# 09_USB_HDMI.net
KiCad netlist of a schematic drawn in Altium Designer
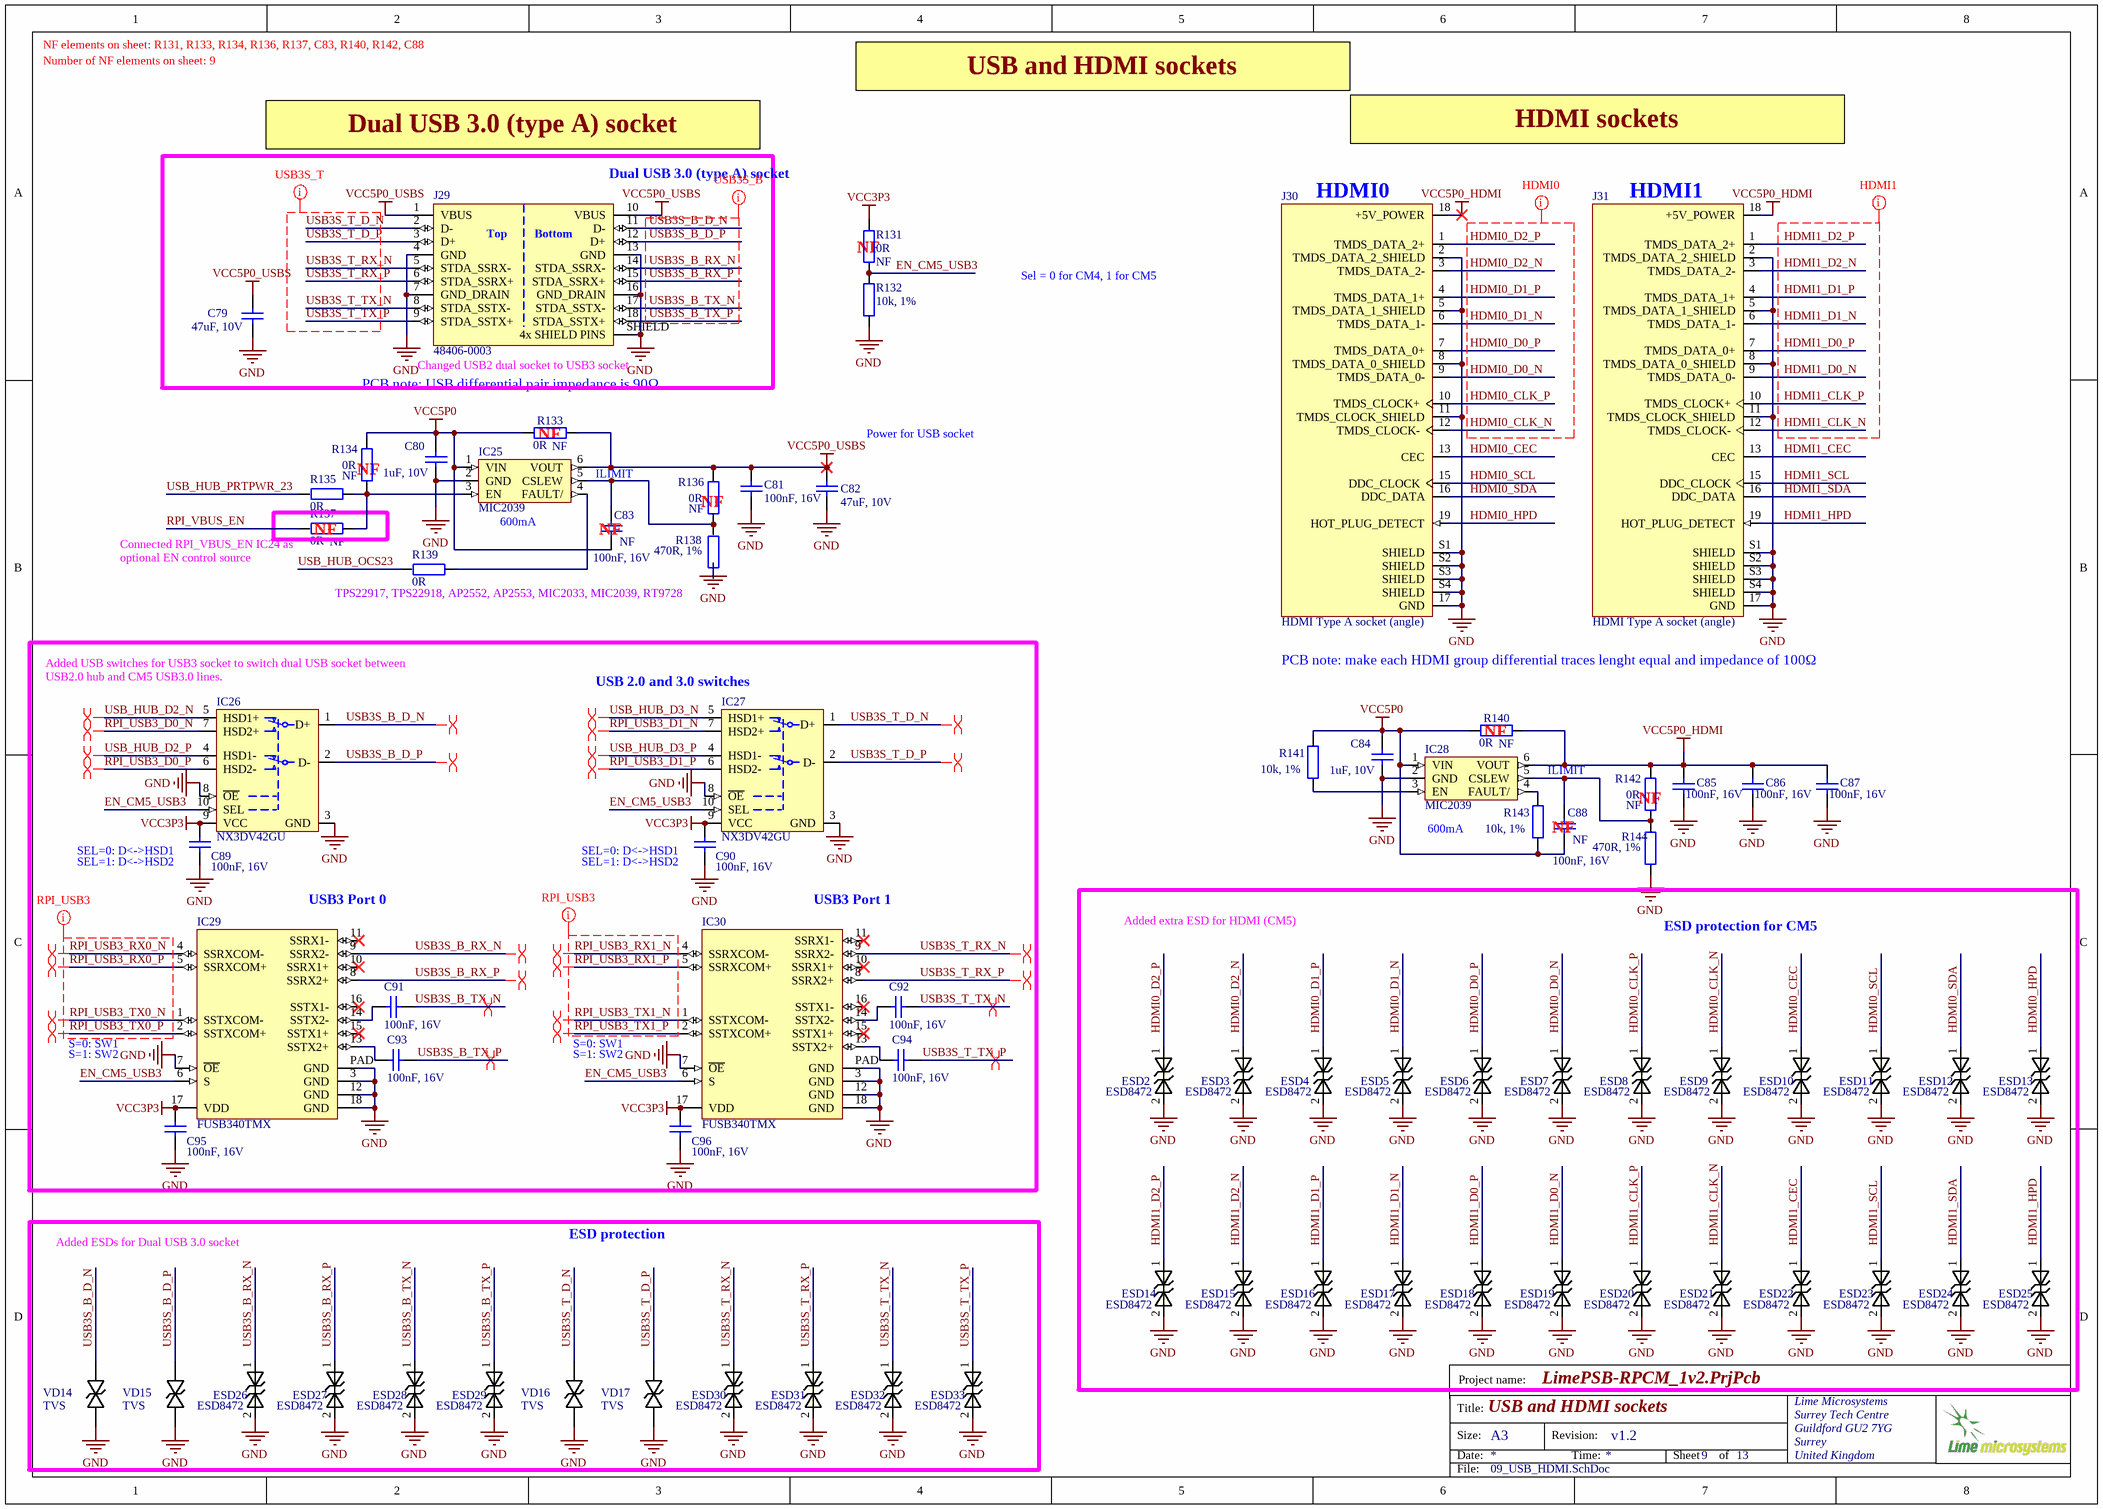
[diagram p0: 09_USB_HDMI.SchDoc]

(export (version "E")
  (design (tool "Eeschema 10.0.6"))
  (components
    (comp (ref "C79")
      (value "47uF, 10V")
      (footprint "CAP1206")
      (fields (field (name "TOLERANCE") "±20%") (field (name "MANUFACTURER") "TDK Corporation"))
      (libsource (lib "LimeFPGAboard_schLib") (part "Cap_1206"))
    )
    (comp (ref "C80")
      (value "1uF, 10V")
      (footprint "CAP0402")
      (fields (field (name "MANUFACTURER") "Yageo"))
      (libsource (lib "") (part "Cap_0402_1"))
    )
    (comp (ref "C81")
      (value "100nF, 16V")
      (footprint "CAP0402")
      (fields
        (field (name "MANUFACTURER") "Murata Electronics")
        (field (name "TOLERANCE") "10 %")
        (field (name "MANUFACTURER PART NUMBER") "GRM155R71C104KA88D")
      )
      (libsource (lib "") (part "Cap_0402_1"))
    )
    (comp (ref "C82")
      (value "47uF, 10V")
      (footprint "CAP1206")
      (fields (field (name "TOLERANCE") "±20%") (field (name "MANUFACTURER") "TDK Corporation"))
      (libsource (lib "LimeFPGAboard_schLib") (part "Cap_1206"))
    )
    (comp (ref "C83")
      (value "100nF, 16V")
      (footprint "CAP0402")
      (fields
        (field (name "ASSEMBLY INFO") "NF")
        (field (name "MANUFACTURER") "Murata Electronics")
        (field (name "TOLERANCE") "10 %")
        (field (name "MANUFACTURER PART NUMBER") "GRM155R71C104KA88D")
      )
      (libsource (lib "") (part "Cap_0402_1"))
    )
    (comp (ref "C84")
      (value "1uF, 10V")
      (footprint "CAP0402")
      (fields (field (name "MANUFACTURER") "Yageo"))
      (libsource (lib "") (part "Cap_0402_1"))
    )
    (comp (ref "C85")
      (value "100nF, 16V")
      (footprint "CAP0402")
      (fields
        (field (name "MANUFACTURER") "Murata Electronics")
        (field (name "TOLERANCE") "10 %")
        (field (name "MANUFACTURER PART NUMBER") "GRM155R71C104KA88D")
      )
      (libsource (lib "") (part "Cap_0402_1"))
    )
    (comp (ref "C86")
      (value "100nF, 16V")
      (footprint "CAP0402")
      (fields
        (field (name "MANUFACTURER") "Murata Electronics")
        (field (name "TOLERANCE") "10 %")
        (field (name "MANUFACTURER PART NUMBER") "GRM155R71C104KA88D")
      )
      (libsource (lib "") (part "Cap_0402_1"))
    )
    (comp (ref "C87")
      (value "100nF, 16V")
      (footprint "CAP0402")
      (fields
        (field (name "MANUFACTURER") "Murata Electronics")
        (field (name "TOLERANCE") "10 %")
        (field (name "MANUFACTURER PART NUMBER") "GRM155R71C104KA88D")
      )
      (libsource (lib "") (part "Cap_0402_1"))
    )
    (comp (ref "C88")
      (value "100nF, 16V")
      (footprint "CAP0402")
      (fields
        (field (name "ASSEMBLY INFO") "NF")
        (field (name "MANUFACTURER") "Murata Electronics")
        (field (name "TOLERANCE") "10 %")
        (field (name "MANUFACTURER PART NUMBER") "GRM155R71C104KA88D")
      )
      (libsource (lib "") (part "Cap_0402_1"))
    )
    (comp (ref "C89")
      (value "100nF, 16V")
      (footprint "CAP0402")
      (fields
        (field (name "MANUFACTURER") "Murata Electronics")
        (field (name "TOLERANCE") "10 %")
        (field (name "MANUFACTURER PART NUMBER") "GRM155R71C104KA88D")
      )
      (libsource (lib "LimeMicroAltiumLib_schLib") (part "Cap_0402"))
    )
    (comp (ref "C90")
      (value "100nF, 16V")
      (footprint "CAP0402")
      (fields
        (field (name "MANUFACTURER") "Murata Electronics")
        (field (name "TOLERANCE") "10 %")
        (field (name "MANUFACTURER PART NUMBER") "GRM155R71C104KA88D")
      )
      (libsource (lib "LimeMicroAltiumLib_schLib") (part "Cap_0402"))
    )
    (comp (ref "C91")
      (value "100nF, 16V")
      (footprint "CAP0402")
      (fields
        (field (name "MANUFACTURER") "Murata Electronics")
        (field (name "TOLERANCE") "10 %")
        (field (name "MANUFACTURER PART NUMBER") "GRM155R71C104KA88D")
      )
      (libsource (lib "LimeMicroAltiumLib_schLib") (part "Cap_0402"))
    )
    (comp (ref "C92")
      (value "100nF, 16V")
      (footprint "CAP0402")
      (fields
        (field (name "MANUFACTURER") "Murata Electronics")
        (field (name "TOLERANCE") "10 %")
        (field (name "MANUFACTURER PART NUMBER") "GRM155R71C104KA88D")
      )
      (libsource (lib "LimeMicroAltiumLib_schLib") (part "Cap_0402"))
    )
    (comp (ref "C93")
      (value "100nF, 16V")
      (footprint "CAP0402")
      (fields
        (field (name "MANUFACTURER") "Murata Electronics")
        (field (name "TOLERANCE") "10 %")
        (field (name "MANUFACTURER PART NUMBER") "GRM155R71C104KA88D")
      )
      (libsource (lib "LimeMicroAltiumLib_schLib") (part "Cap_0402"))
    )
    (comp (ref "C94")
      (value "100nF, 16V")
      (footprint "CAP0402")
      (fields
        (field (name "MANUFACTURER") "Murata Electronics")
        (field (name "TOLERANCE") "10 %")
        (field (name "MANUFACTURER PART NUMBER") "GRM155R71C104KA88D")
      )
      (libsource (lib "LimeMicroAltiumLib_schLib") (part "Cap_0402"))
    )
    (comp (ref "C95")
      (value "100nF, 16V")
      (footprint "CAP0402")
      (fields
        (field (name "MANUFACTURER") "Murata Electronics")
        (field (name "TOLERANCE") "10 %")
        (field (name "MANUFACTURER PART NUMBER") "GRM155R71C104KA88D")
      )
      (libsource (lib "LimeMicroAltiumLib_schLib") (part "Cap_0402"))
    )
    (comp (ref "C96")
      (value "100nF, 16V")
      (footprint "CAP0402")
      (fields
        (field (name "MANUFACTURER") "Murata Electronics")
        (field (name "TOLERANCE") "10 %")
        (field (name "MANUFACTURER PART NUMBER") "GRM155R71C104KA88D")
      )
      (libsource (lib "LimeMicroAltiumLib_schLib") (part "Cap_0402"))
    )
    (comp (ref "ESD2")
      (value "ESD8472")
      (footprint "ESD8472_X3DFN2")
      (fields (field (name "MANUFACTURER") "ON Semiconductor"))
      (libsource (lib "LimeMicroAltiumLib_schLib") (part "ESD8472"))
    )
    (comp (ref "ESD3")
      (value "ESD8472")
      (footprint "ESD8472_X3DFN2")
      (fields (field (name "MANUFACTURER") "ON Semiconductor"))
      (libsource (lib "LimeMicroAltiumLib_schLib") (part "ESD8472"))
    )
    (comp (ref "ESD4")
      (value "ESD8472")
      (footprint "ESD8472_X3DFN2")
      (fields (field (name "MANUFACTURER") "ON Semiconductor"))
      (libsource (lib "LimeMicroAltiumLib_schLib") (part "ESD8472"))
    )
    (comp (ref "ESD5")
      (value "ESD8472")
      (footprint "ESD8472_X3DFN2")
      (fields (field (name "MANUFACTURER") "ON Semiconductor"))
      (libsource (lib "LimeMicroAltiumLib_schLib") (part "ESD8472"))
    )
    (comp (ref "ESD6")
      (value "ESD8472")
      (footprint "ESD8472_X3DFN2")
      (fields (field (name "MANUFACTURER") "ON Semiconductor"))
      (libsource (lib "LimeMicroAltiumLib_schLib") (part "ESD8472"))
    )
    (comp (ref "ESD7")
      (value "ESD8472")
      (footprint "ESD8472_X3DFN2")
      (fields (field (name "MANUFACTURER") "ON Semiconductor"))
      (libsource (lib "LimeMicroAltiumLib_schLib") (part "ESD8472"))
    )
    (comp (ref "ESD8")
      (value "ESD8472")
      (footprint "ESD8472_X3DFN2")
      (fields (field (name "MANUFACTURER") "ON Semiconductor"))
      (libsource (lib "LimeMicroAltiumLib_schLib") (part "ESD8472"))
    )
    (comp (ref "ESD9")
      (value "ESD8472")
      (footprint "ESD8472_X3DFN2")
      (fields (field (name "MANUFACTURER") "ON Semiconductor"))
      (libsource (lib "LimeMicroAltiumLib_schLib") (part "ESD8472"))
    )
    (comp (ref "ESD10")
      (value "ESD8472")
      (footprint "ESD8472_X3DFN2")
      (fields (field (name "MANUFACTURER") "ON Semiconductor"))
      (libsource (lib "LimeMicroAltiumLib_schLib") (part "ESD8472"))
    )
    (comp (ref "ESD11")
      (value "ESD8472")
      (footprint "ESD8472_X3DFN2")
      (fields (field (name "MANUFACTURER") "ON Semiconductor"))
      (libsource (lib "LimeMicroAltiumLib_schLib") (part "ESD8472"))
    )
    (comp (ref "ESD12")
      (value "ESD8472")
      (footprint "ESD8472_X3DFN2")
      (fields (field (name "MANUFACTURER") "ON Semiconductor"))
      (libsource (lib "LimeMicroAltiumLib_schLib") (part "ESD8472"))
    )
    (comp (ref "ESD13")
      (value "ESD8472")
      (footprint "ESD8472_X3DFN2")
      (fields (field (name "MANUFACTURER") "ON Semiconductor"))
      (libsource (lib "LimeMicroAltiumLib_schLib") (part "ESD8472"))
    )
    (comp (ref "ESD14")
      (value "ESD8472")
      (footprint "ESD8472_X3DFN2")
      (fields (field (name "MANUFACTURER") "ON Semiconductor"))
      (libsource (lib "LimeMicroAltiumLib_schLib") (part "ESD8472"))
    )
    (comp (ref "ESD15")
      (value "ESD8472")
      (footprint "ESD8472_X3DFN2")
      (fields (field (name "MANUFACTURER") "ON Semiconductor"))
      (libsource (lib "LimeMicroAltiumLib_schLib") (part "ESD8472"))
    )
    (comp (ref "ESD16")
      (value "ESD8472")
      (footprint "ESD8472_X3DFN2")
      (fields (field (name "MANUFACTURER") "ON Semiconductor"))
      (libsource (lib "LimeMicroAltiumLib_schLib") (part "ESD8472"))
    )
    (comp (ref "ESD17")
      (value "ESD8472")
      (footprint "ESD8472_X3DFN2")
      (fields (field (name "MANUFACTURER") "ON Semiconductor"))
      (libsource (lib "LimeMicroAltiumLib_schLib") (part "ESD8472"))
    )
    (comp (ref "ESD18")
      (value "ESD8472")
      (footprint "ESD8472_X3DFN2")
      (fields (field (name "MANUFACTURER") "ON Semiconductor"))
      (libsource (lib "LimeMicroAltiumLib_schLib") (part "ESD8472"))
    )
    (comp (ref "ESD19")
      (value "ESD8472")
      (footprint "ESD8472_X3DFN2")
      (fields (field (name "MANUFACTURER") "ON Semiconductor"))
      (libsource (lib "LimeMicroAltiumLib_schLib") (part "ESD8472"))
    )
    (comp (ref "ESD20")
      (value "ESD8472")
      (footprint "ESD8472_X3DFN2")
      (fields (field (name "MANUFACTURER") "ON Semiconductor"))
      (libsource (lib "LimeMicroAltiumLib_schLib") (part "ESD8472"))
    )
    (comp (ref "ESD21")
      (value "ESD8472")
      (footprint "ESD8472_X3DFN2")
      (fields (field (name "MANUFACTURER") "ON Semiconductor"))
      (libsource (lib "LimeMicroAltiumLib_schLib") (part "ESD8472"))
    )
    (comp (ref "ESD22")
      (value "ESD8472")
      (footprint "ESD8472_X3DFN2")
      (fields (field (name "MANUFACTURER") "ON Semiconductor"))
      (libsource (lib "LimeMicroAltiumLib_schLib") (part "ESD8472"))
    )
    (comp (ref "ESD23")
      (value "ESD8472")
      (footprint "ESD8472_X3DFN2")
      (fields (field (name "MANUFACTURER") "ON Semiconductor"))
      (libsource (lib "LimeMicroAltiumLib_schLib") (part "ESD8472"))
    )
    (comp (ref "ESD24")
      (value "ESD8472")
      (footprint "ESD8472_X3DFN2")
      (fields (field (name "MANUFACTURER") "ON Semiconductor"))
      (libsource (lib "LimeMicroAltiumLib_schLib") (part "ESD8472"))
    )
    (comp (ref "ESD25")
      (value "ESD8472")
      (footprint "ESD8472_X3DFN2")
      (fields (field (name "MANUFACTURER") "ON Semiconductor"))
      (libsource (lib "LimeMicroAltiumLib_schLib") (part "ESD8472"))
    )
    (comp (ref "ESD26")
      (value "ESD8472")
      (footprint "ESD8472_X3DFN2")
      (fields (field (name "MANUFACTURER") "ON Semiconductor"))
      (libsource (lib "LimeMicroAltiumLib_schLib") (part "ESD8472"))
    )
    (comp (ref "ESD27")
      (value "ESD8472")
      (footprint "ESD8472_X3DFN2")
      (fields (field (name "MANUFACTURER") "ON Semiconductor"))
      (libsource (lib "LimeMicroAltiumLib_schLib") (part "ESD8472"))
    )
    (comp (ref "ESD28")
      (value "ESD8472")
      (footprint "ESD8472_X3DFN2")
      (fields (field (name "MANUFACTURER") "ON Semiconductor"))
      (libsource (lib "LimeMicroAltiumLib_schLib") (part "ESD8472"))
    )
    (comp (ref "ESD29")
      (value "ESD8472")
      (footprint "ESD8472_X3DFN2")
      (fields (field (name "MANUFACTURER") "ON Semiconductor"))
      (libsource (lib "LimeMicroAltiumLib_schLib") (part "ESD8472"))
    )
    (comp (ref "ESD30")
      (value "ESD8472")
      (footprint "ESD8472_X3DFN2")
      (fields (field (name "MANUFACTURER") "ON Semiconductor"))
      (libsource (lib "LimeMicroAltiumLib_schLib") (part "ESD8472"))
    )
    (comp (ref "ESD31")
      (value "ESD8472")
      (footprint "ESD8472_X3DFN2")
      (fields (field (name "MANUFACTURER") "ON Semiconductor"))
      (libsource (lib "LimeMicroAltiumLib_schLib") (part "ESD8472"))
    )
    (comp (ref "ESD32")
      (value "ESD8472")
      (footprint "ESD8472_X3DFN2")
      (fields (field (name "MANUFACTURER") "ON Semiconductor"))
      (libsource (lib "LimeMicroAltiumLib_schLib") (part "ESD8472"))
    )
    (comp (ref "ESD33")
      (value "ESD8472")
      (footprint "ESD8472_X3DFN2")
      (fields (field (name "MANUFACTURER") "ON Semiconductor"))
      (libsource (lib "LimeMicroAltiumLib_schLib") (part "ESD8472"))
    )
    (comp (ref "IC25")
      (value "MIC2039")
      (footprint "SOT23-6")
      (fields (field (name "MANUFACTURER") "Microchip"))
      (libsource (lib "LimeMicroAltiumLib_schLib_r04") (part "MIC2033_power_switch"))
    )
    (comp (ref "IC26")
      (value "NX3DV42GU")
      (footprint "FSUSB42UMX")
      (fields (field (name "MANUFACTURER") "NXP Semiconductors"))
      (libsource (lib "LimeMicroAltiumLib_schLib_r01") (part "FSUSB42UMX"))
    )
    (comp (ref "IC27")
      (value "NX3DV42GU")
      (footprint "FSUSB42UMX")
      (fields (field (name "MANUFACTURER") "NXP Semiconductors"))
      (libsource (lib "LimeMicroAltiumLib_schLib_r01") (part "FSUSB42UMX"))
    )
    (comp (ref "IC28")
      (value "MIC2039")
      (footprint "SOT23-6")
      (fields (field (name "MANUFACTURER") "Microchip"))
      (libsource (lib "LimeMicroAltiumLib_schLib_r04") (part "MIC2033_power_switch"))
    )
    (comp (ref "IC29")
      (value "FUSB340TMX")
      (footprint "FUSB340TMX_USB_switch_18-XFQFN")
      (fields (field (name "MANUFACTURER") "ON Semiconductor / Fairchild"))
      (libsource (lib "LimeMicroAltiumLib") (part "FUSB340TMX_USB_switch"))
    )
    (comp (ref "IC30")
      (value "FUSB340TMX")
      (footprint "FUSB340TMX_USB_switch_18-XFQFN")
      (fields (field (name "MANUFACTURER") "ON Semiconductor / Fairchild"))
      (libsource (lib "LimeMicroAltiumLib") (part "FUSB340TMX_USB_switch"))
    )
    (comp (ref "J29")
      (value "48406-0003")
      (footprint "Dual_USB_48406-0003_Molex")
      (fields (field (name "MANUFACTURER") "Molex"))
      (libsource (lib "LimeMicroAltiumLib") (part "Dual_USB_48406-0003_Molex"))
    )
    (comp (ref "J30")
      (value "HDMI Type A socket (angle)")
      (footprint "HDMI_HD01-19-RA-TH")
      (fields (field (name "MANUFACTURER") "CUI Devices"))
      (libsource (lib "LimeMicroAltiumLib_schLib_r04") (part "HDMI_HD01-19-RA-TH"))
    )
    (comp (ref "J31")
      (value "HDMI Type A socket (angle)")
      (footprint "HDMI_HD01-19-RA-TH")
      (fields (field (name "MANUFACTURER") "CUI Devices"))
      (libsource (lib "LimeMicroAltiumLib_schLib_r04") (part "HDMI_HD01-19-RA-TH"))
    )
    (comp (ref "R131")
      (value "0R")
      (footprint "RES0402")
      (fields
        (field (name "ASSEMBLY INFO") "NF")
        (field (name "MANUFACTURER") "Yageo")
        (field (name "TOLERANCE") "Jumper")
      )
      (libsource (lib "") (part "Res_0402_1"))
    )
    (comp (ref "R132")
      (value "10k, 1%")
      (footprint "RES0402")
      (fields (field (name "MANUFACTURER") "Yageo") (field (name "TOLERANCE") "±1%"))
      (libsource (lib "") (part "Res_0402_1"))
    )
    (comp (ref "R133")
      (value "0R")
      (footprint "RES0402")
      (fields
        (field (name "ASSEMBLY INFO") "NF")
        (field (name "MANUFACTURER") "Yageo")
        (field (name "TOLERANCE") "Jumper")
      )
      (libsource (lib "LimeMicroAltiumLib_schLib") (part "Res_0402"))
    )
    (comp (ref "R134")
      (value "0R")
      (footprint "RES0402")
      (fields
        (field (name "ASSEMBLY INFO") "NF")
        (field (name "MANUFACTURER") "Yageo")
        (field (name "TOLERANCE") "Jumper")
      )
      (libsource (lib "LimeMicroAltiumLib_schLib") (part "Res_0402"))
    )
    (comp (ref "R135")
      (value "0R")
      (footprint "RES0402")
      (fields (field (name "MANUFACTURER") "Yageo") (field (name "TOLERANCE") "Jumper"))
      (libsource (lib "LimeMicroAltiumLib_schLib") (part "Res_0402"))
    )
    (comp (ref "R136")
      (value "0R")
      (footprint "RES0402")
      (fields
        (field (name "ASSEMBLY INFO") "NF")
        (field (name "MANUFACTURER") "Yageo")
        (field (name "TOLERANCE") "Jumper")
      )
      (libsource (lib "LimeMicroAltiumLib_schLib") (part "Res_0402"))
    )
    (comp (ref "R137")
      (value "0R")
      (footprint "RES0402")
      (fields
        (field (name "ASSEMBLY INFO") "NF")
        (field (name "MANUFACTURER") "Yageo")
        (field (name "TOLERANCE") "Jumper")
      )
      (libsource (lib "LimeMicroAltiumLib_schLib") (part "Res_0402"))
    )
    (comp (ref "R138")
      (value "470R, 1%")
      (footprint "RES0402")
      (fields (field (name "TOLERANCE") "1%") (field (name "MANUFACTURER") "Yageo"))
      (libsource (lib "LimeMicroAltiumLib_schLib") (part "Res_0402"))
    )
    (comp (ref "R139")
      (value "0R")
      (footprint "RES0402")
      (fields (field (name "MANUFACTURER") "Yageo") (field (name "TOLERANCE") "Jumper"))
      (libsource (lib "LimeMicroAltiumLib_schLib") (part "Res_0402"))
    )
    (comp (ref "R140")
      (value "0R")
      (footprint "RES0402")
      (fields
        (field (name "ASSEMBLY INFO") "NF")
        (field (name "MANUFACTURER") "Yageo")
        (field (name "TOLERANCE") "Jumper")
      )
      (libsource (lib "LimeMicroAltiumLib_schLib") (part "Res_0402"))
    )
    (comp (ref "R141")
      (value "10k, 1%")
      (footprint "RES0402")
      (fields (field (name "MANUFACTURER") "Yageo") (field (name "TOLERANCE") "±1%"))
      (libsource (lib "") (part "Res_0402_1"))
    )
    (comp (ref "R142")
      (value "0R")
      (footprint "RES0402")
      (fields
        (field (name "ASSEMBLY INFO") "NF")
        (field (name "MANUFACTURER") "Yageo")
        (field (name "TOLERANCE") "Jumper")
      )
      (libsource (lib "LimeMicroAltiumLib_schLib") (part "Res_0402"))
    )
    (comp (ref "R143")
      (value "10k, 1%")
      (footprint "RES0402")
      (fields (field (name "MANUFACTURER") "Yageo") (field (name "TOLERANCE") "±1%"))
      (libsource (lib "") (part "Res_0402_1"))
    )
    (comp (ref "R144")
      (value "470R, 1%")
      (footprint "RES0402")
      (fields (field (name "TOLERANCE") "1%") (field (name "MANUFACTURER") "Yageo"))
      (libsource (lib "LimeMicroAltiumLib_schLib") (part "Res_0402"))
    )
    (comp (ref "VD14")
      (value "TVS")
      (footprint "SOD323")
      (fields
        (field (name "MANUFACTURER PART NUMBER") "SD03LCC")
        (field (name "MANUFACTURER") "Sangdest Microelectronics")
      )
      (libsource (lib "LimeNet-Micro_2v1-SDR") (part "DIODE_TVS"))
    )
    (comp (ref "VD15")
      (value "TVS")
      (footprint "SOD323")
      (fields
        (field (name "MANUFACTURER PART NUMBER") "SD03LCC")
        (field (name "MANUFACTURER") "Sangdest Microelectronics")
      )
      (libsource (lib "LimeNet-Micro_2v1-SDR") (part "DIODE_TVS"))
    )
    (comp (ref "VD16")
      (value "TVS")
      (footprint "SOD323")
      (fields
        (field (name "MANUFACTURER PART NUMBER") "SD03LCC")
        (field (name "MANUFACTURER") "Sangdest Microelectronics")
      )
      (libsource (lib "LimeNet-Micro_2v1-SDR") (part "DIODE_TVS"))
    )
    (comp (ref "VD17")
      (value "TVS")
      (footprint "SOD323")
      (fields
        (field (name "MANUFACTURER PART NUMBER") "SD03LCC")
        (field (name "MANUFACTURER") "Sangdest Microelectronics")
      )
      (libsource (lib "LimeNet-Micro_2v1-SDR") (part "DIODE_TVS"))
    )
  )
  (nets
    (net (code "1") (name "/EN_CM5_USB3") (class "Default")
      (node (ref "IC26") (pin "10") (pinfunction "SEL_10") (pintype "input"))
      (node (ref "IC27") (pin "10") (pinfunction "SEL_10") (pintype "input"))
      (node (ref "IC29") (pin "6") (pinfunction "S_6") (pintype "input"))
      (node (ref "IC30") (pin "6") (pinfunction "S_6") (pintype "input"))
      (node (ref "R131") (pin "1") (pinfunction "1_1") (pintype "passive"))
      (node (ref "R132") (pin "1") (pinfunction "1_1") (pintype "passive"))
    )
    (net (code "2") (name "/HDMI0_CEC") (class "Default")
      (node (ref "ESD10") (pin "1") (pinfunction "1_1") (pintype "passive"))
      (node (ref "J30") (pin "13") (pinfunction "CEC_13") (pintype "bidirectional"))
    )
    (net (code "3") (name "/HDMI0_CLK_N") (class "Default")
      (node (ref "ESD9") (pin "1") (pinfunction "1_1") (pintype "passive"))
      (node (ref "J30") (pin "12") (pinfunction "TMDS_CLOCK-_12") (pintype "bidirectional"))
    )
    (net (code "4") (name "/HDMI0_CLK_P") (class "Default")
      (node (ref "ESD8") (pin "1") (pinfunction "1_1") (pintype "passive"))
      (node (ref "J30") (pin "10") (pinfunction "TMDS_CLOCK+_10") (pintype "bidirectional"))
    )
    (net (code "5") (name "/HDMI0_D0_N") (class "Default")
      (node (ref "ESD7") (pin "1") (pinfunction "1_1") (pintype "passive"))
      (node (ref "J30") (pin "9") (pinfunction "TMDS_DATA_0-_9") (pintype "bidirectional"))
    )
    (net (code "6") (name "/HDMI0_D0_P") (class "Default")
      (node (ref "ESD6") (pin "1") (pinfunction "1_1") (pintype "passive"))
      (node (ref "J30") (pin "7") (pinfunction "TMDS_DATA_0+_7") (pintype "bidirectional"))
    )
    (net (code "7") (name "/HDMI0_D1_N") (class "Default")
      (node (ref "ESD5") (pin "1") (pinfunction "1_1") (pintype "passive"))
      (node (ref "J30") (pin "6") (pinfunction "TMDS_DATA_1-_6") (pintype "bidirectional"))
    )
    (net (code "8") (name "/HDMI0_D1_P") (class "Default")
      (node (ref "ESD4") (pin "1") (pinfunction "1_1") (pintype "passive"))
      (node (ref "J30") (pin "4") (pinfunction "TMDS_DATA_1+_4") (pintype "bidirectional"))
    )
    (net (code "9") (name "/HDMI0_D2_N") (class "Default")
      (node (ref "ESD3") (pin "1") (pinfunction "1_1") (pintype "passive"))
      (node (ref "J30") (pin "3") (pinfunction "TMDS_DATA_2-_3") (pintype "bidirectional"))
    )
    (net (code "10") (name "/HDMI0_D2_P") (class "Default")
      (node (ref "ESD2") (pin "1") (pinfunction "1_1") (pintype "passive"))
      (node (ref "J30") (pin "1") (pinfunction "TMDS_DATA_2+_1") (pintype "bidirectional"))
    )
    (net (code "11") (name "/HDMI0_HPD") (class "Default")
      (node (ref "ESD13") (pin "1") (pinfunction "1_1") (pintype "passive"))
      (node (ref "J30") (pin "19") (pinfunction "HOT_PLUG_DETECT_19") (pintype "input"))
    )
    (net (code "12") (name "/HDMI0_SCL") (class "Default")
      (node (ref "ESD11") (pin "1") (pinfunction "1_1") (pintype "passive"))
      (node (ref "J30") (pin "15") (pinfunction "DDC_CLOCK_15") (pintype "bidirectional"))
    )
    (net (code "13") (name "/HDMI0_SDA") (class "Default")
      (node (ref "ESD12") (pin "1") (pinfunction "1_1") (pintype "passive"))
      (node (ref "J30") (pin "16") (pinfunction "DDC_DATA_16") (pintype "bidirectional"))
    )
    (net (code "14") (name "/HDMI1_CEC") (class "Default")
      (node (ref "ESD22") (pin "1") (pinfunction "1_1") (pintype "passive"))
      (node (ref "J31") (pin "13") (pinfunction "CEC_13") (pintype "bidirectional"))
    )
    (net (code "15") (name "/HDMI1_CLK_N") (class "Default")
      (node (ref "ESD21") (pin "1") (pinfunction "1_1") (pintype "passive"))
      (node (ref "J31") (pin "12") (pinfunction "TMDS_CLOCK-_12") (pintype "bidirectional"))
    )
    (net (code "16") (name "/HDMI1_CLK_P") (class "Default")
      (node (ref "ESD20") (pin "1") (pinfunction "1_1") (pintype "passive"))
      (node (ref "J31") (pin "10") (pinfunction "TMDS_CLOCK+_10") (pintype "bidirectional"))
    )
    (net (code "17") (name "/HDMI1_D0_N") (class "Default")
      (node (ref "ESD19") (pin "1") (pinfunction "1_1") (pintype "passive"))
      (node (ref "J31") (pin "9") (pinfunction "TMDS_DATA_0-_9") (pintype "bidirectional"))
    )
    (net (code "18") (name "/HDMI1_D0_P") (class "Default")
      (node (ref "ESD18") (pin "1") (pinfunction "1_1") (pintype "passive"))
      (node (ref "J31") (pin "7") (pinfunction "TMDS_DATA_0+_7") (pintype "bidirectional"))
    )
    (net (code "19") (name "/HDMI1_D1_N") (class "Default")
      (node (ref "ESD17") (pin "1") (pinfunction "1_1") (pintype "passive"))
      (node (ref "J31") (pin "6") (pinfunction "TMDS_DATA_1-_6") (pintype "bidirectional"))
    )
    (net (code "20") (name "/HDMI1_D1_P") (class "Default")
      (node (ref "ESD16") (pin "1") (pinfunction "1_1") (pintype "passive"))
      (node (ref "J31") (pin "4") (pinfunction "TMDS_DATA_1+_4") (pintype "bidirectional"))
    )
    (net (code "21") (name "/HDMI1_D2_N") (class "Default")
      (node (ref "ESD15") (pin "1") (pinfunction "1_1") (pintype "passive"))
      (node (ref "J31") (pin "3") (pinfunction "TMDS_DATA_2-_3") (pintype "bidirectional"))
    )
    (net (code "22") (name "/HDMI1_D2_P") (class "Default")
      (node (ref "ESD14") (pin "1") (pinfunction "1_1") (pintype "passive"))
      (node (ref "J31") (pin "1") (pinfunction "TMDS_DATA_2+_1") (pintype "bidirectional"))
    )
    (net (code "23") (name "/HDMI1_HPD") (class "Default")
      (node (ref "ESD25") (pin "1") (pinfunction "1_1") (pintype "passive"))
      (node (ref "J31") (pin "19") (pinfunction "HOT_PLUG_DETECT_19") (pintype "input"))
    )
    (net (code "24") (name "/HDMI1_SCL") (class "Default")
      (node (ref "ESD23") (pin "1") (pinfunction "1_1") (pintype "passive"))
      (node (ref "J31") (pin "15") (pinfunction "DDC_CLOCK_15") (pintype "bidirectional"))
    )
    (net (code "25") (name "/HDMI1_SDA") (class "Default")
      (node (ref "ESD24") (pin "1") (pinfunction "1_1") (pintype "passive"))
      (node (ref "J31") (pin "16") (pinfunction "DDC_DATA_16") (pintype "bidirectional"))
    )
    (net (code "26") (name "/RPI_USB3_D0_N") (class "Default")
      (node (ref "IC26") (pin "7") (pinfunction "HSD2+_7") (pintype "passive"))
    )
    (net (code "27") (name "/RPI_USB3_D0_P") (class "Default")
      (node (ref "IC26") (pin "6") (pinfunction "HSD2-_6") (pintype "passive"))
    )
    (net (code "28") (name "/RPI_USB3_D1_N") (class "Default")
      (node (ref "IC27") (pin "7") (pinfunction "HSD2+_7") (pintype "passive"))
    )
    (net (code "29") (name "/RPI_USB3_D1_P") (class "Default")
      (node (ref "IC27") (pin "6") (pinfunction "HSD2-_6") (pintype "passive"))
    )
    (net (code "30") (name "/RPI_USB3_RX0_N") (class "Default")
      (node (ref "IC29") (pin "4") (pinfunction "SSRXCOM-_4") (pintype "bidirectional"))
    )
    (net (code "31") (name "/RPI_USB3_RX0_P") (class "Default")
      (node (ref "IC29") (pin "5") (pinfunction "SSRXCOM+_5") (pintype "bidirectional"))
    )
    (net (code "32") (name "/RPI_USB3_RX1_N") (class "Default")
      (node (ref "IC30") (pin "4") (pinfunction "SSRXCOM-_4") (pintype "bidirectional"))
    )
    (net (code "33") (name "/RPI_USB3_RX1_P") (class "Default")
      (node (ref "IC30") (pin "5") (pinfunction "SSRXCOM+_5") (pintype "bidirectional"))
    )
    (net (code "34") (name "/RPI_USB3_TX0_N") (class "Default")
      (node (ref "IC29") (pin "1") (pinfunction "SSTXCOM-_1") (pintype "bidirectional"))
    )
    (net (code "35") (name "/RPI_USB3_TX0_P") (class "Default")
      (node (ref "IC29") (pin "2") (pinfunction "SSTXCOM+_2") (pintype "bidirectional"))
    )
    (net (code "36") (name "/RPI_USB3_TX1_N") (class "Default")
      (node (ref "IC30") (pin "1") (pinfunction "SSTXCOM-_1") (pintype "bidirectional"))
    )
    (net (code "37") (name "/RPI_USB3_TX1_P") (class "Default")
      (node (ref "IC30") (pin "2") (pinfunction "SSTXCOM+_2") (pintype "bidirectional"))
    )
    (net (code "38") (name "/RPI_VBUS_EN") (class "Default")
      (node (ref "R137") (pin "2") (pinfunction "2_2") (pintype "passive"))
    )
    (net (code "39") (name "/USB3S_B_D_N") (class "Default")
      (node (ref "IC26") (pin "1") (pinfunction "D+_1") (pintype "passive"))
      (node (ref "J29") (pin "11") (pinfunction "D-_11") (pintype "bidirectional"))
      (node (ref "VD14") (pin "A") (pinfunction "A_A") (pintype "passive"))
    )
    (net (code "40") (name "/USB3S_B_D_P") (class "Default")
      (node (ref "IC26") (pin "2") (pinfunction "D-_2") (pintype "passive"))
      (node (ref "J29") (pin "12") (pinfunction "D+_12") (pintype "bidirectional"))
      (node (ref "VD15") (pin "A") (pinfunction "A_A") (pintype "passive"))
    )
    (net (code "41") (name "/USB3S_B_RX_N") (class "Default")
      (node (ref "ESD26") (pin "1") (pinfunction "1_1") (pintype "passive"))
      (node (ref "IC29") (pin "9") (pinfunction "SSRX2-_9") (pintype "bidirectional"))
      (node (ref "J29") (pin "14") (pinfunction "STDA_SSRX-_14") (pintype "bidirectional"))
    )
    (net (code "42") (name "/USB3S_B_RX_P") (class "Default")
      (node (ref "ESD27") (pin "1") (pinfunction "1_1") (pintype "passive"))
      (node (ref "IC29") (pin "8") (pinfunction "SSRX2+_8") (pintype "bidirectional"))
      (node (ref "J29") (pin "15") (pinfunction "STDA_SSRX+_15") (pintype "bidirectional"))
    )
    (net (code "43") (name "/USB3S_B_TX_N") (class "Default")
      (node (ref "C91") (pin "2") (pinfunction "2_2") (pintype "passive"))
      (node (ref "ESD28") (pin "1") (pinfunction "1_1") (pintype "passive"))
      (node (ref "J29") (pin "17") (pinfunction "STDA_SSTX-_17") (pintype "bidirectional"))
    )
    (net (code "44") (name "/USB3S_B_TX_P") (class "Default")
      (node (ref "C93") (pin "2") (pinfunction "2_2") (pintype "passive"))
      (node (ref "ESD29") (pin "1") (pinfunction "1_1") (pintype "passive"))
      (node (ref "J29") (pin "18") (pinfunction "STDA_SSTX+_18") (pintype "bidirectional"))
    )
    (net (code "45") (name "/USB3S_T_D_N") (class "Default")
      (node (ref "IC27") (pin "1") (pinfunction "D+_1") (pintype "passive"))
      (node (ref "J29") (pin "2") (pinfunction "D-_2") (pintype "bidirectional"))
      (node (ref "VD16") (pin "A") (pinfunction "A_A") (pintype "passive"))
    )
    (net (code "46") (name "/USB3S_T_D_P") (class "Default")
      (node (ref "IC27") (pin "2") (pinfunction "D-_2") (pintype "passive"))
      (node (ref "J29") (pin "3") (pinfunction "D+_3") (pintype "bidirectional"))
      (node (ref "VD17") (pin "A") (pinfunction "A_A") (pintype "passive"))
    )
    (net (code "47") (name "/USB3S_T_RX_N") (class "Default")
      (node (ref "ESD30") (pin "1") (pinfunction "1_1") (pintype "passive"))
      (node (ref "IC30") (pin "9") (pinfunction "SSRX2-_9") (pintype "bidirectional"))
      (node (ref "J29") (pin "5") (pinfunction "STDA_SSRX-_5") (pintype "bidirectional"))
    )
    (net (code "48") (name "/USB3S_T_RX_P") (class "Default")
      (node (ref "ESD31") (pin "1") (pinfunction "1_1") (pintype "passive"))
      (node (ref "IC30") (pin "8") (pinfunction "SSRX2+_8") (pintype "bidirectional"))
      (node (ref "J29") (pin "6") (pinfunction "STDA_SSRX+_6") (pintype "bidirectional"))
    )
    (net (code "49") (name "/USB3S_T_TX_N") (class "Default")
      (node (ref "C92") (pin "2") (pinfunction "2_2") (pintype "passive"))
      (node (ref "ESD32") (pin "1") (pinfunction "1_1") (pintype "passive"))
      (node (ref "J29") (pin "8") (pinfunction "STDA_SSTX-_8") (pintype "bidirectional"))
    )
    (net (code "50") (name "/USB3S_T_TX_P") (class "Default")
      (node (ref "C94") (pin "2") (pinfunction "2_2") (pintype "passive"))
      (node (ref "ESD33") (pin "1") (pinfunction "1_1") (pintype "passive"))
      (node (ref "J29") (pin "9") (pinfunction "STDA_SSTX+_9") (pintype "bidirectional"))
    )
    (net (code "51") (name "/USB_HUB_D2_N") (class "Default")
      (node (ref "IC26") (pin "5") (pinfunction "HSD1+_5") (pintype "passive"))
    )
    (net (code "52") (name "/USB_HUB_D2_P") (class "Default")
      (node (ref "IC26") (pin "4") (pinfunction "HSD1-_4") (pintype "passive"))
    )
    (net (code "53") (name "/USB_HUB_D3_N") (class "Default")
      (node (ref "IC27") (pin "5") (pinfunction "HSD1+_5") (pintype "passive"))
    )
    (net (code "54") (name "/USB_HUB_D3_P") (class "Default")
      (node (ref "IC27") (pin "4") (pinfunction "HSD1-_4") (pintype "passive"))
    )
    (net (code "55") (name "/USB_HUB_OCS23") (class "Default")
      (node (ref "R139") (pin "2") (pinfunction "2_2") (pintype "passive"))
    )
    (net (code "56") (name "/USB_HUB_PRTPWR_23") (class "Default")
      (node (ref "R135") (pin "2") (pinfunction "2_2") (pintype "passive"))
    )
    (net (code "57") (name "GND") (class "Default")
      (node (ref "C79") (pin "1") (pinfunction "1_1") (pintype "passive"))
      (node (ref "C80") (pin "2") (pinfunction "2_2") (pintype "passive"))
      (node (ref "C81") (pin "2") (pinfunction "2_2") (pintype "passive"))
      (node (ref "C82") (pin "1") (pinfunction "1_1") (pintype "passive"))
      (node (ref "C84") (pin "2") (pinfunction "2_2") (pintype "passive"))
      (node (ref "C85") (pin "2") (pinfunction "2_2") (pintype "passive"))
      (node (ref "C86") (pin "2") (pinfunction "2_2") (pintype "passive"))
      (node (ref "C87") (pin "2") (pinfunction "2_2") (pintype "passive"))
      (node (ref "C89") (pin "2") (pinfunction "2_2") (pintype "passive"))
      (node (ref "C90") (pin "2") (pinfunction "2_2") (pintype "passive"))
      (node (ref "C95") (pin "2") (pinfunction "2_2") (pintype "passive"))
      (node (ref "C96") (pin "2") (pinfunction "2_2") (pintype "passive"))
      (node (ref "ESD10") (pin "2") (pinfunction "2_2") (pintype "passive"))
      (node (ref "ESD11") (pin "2") (pinfunction "2_2") (pintype "passive"))
      (node (ref "ESD12") (pin "2") (pinfunction "2_2") (pintype "passive"))
      (node (ref "ESD13") (pin "2") (pinfunction "2_2") (pintype "passive"))
      (node (ref "ESD14") (pin "2") (pinfunction "2_2") (pintype "passive"))
      (node (ref "ESD15") (pin "2") (pinfunction "2_2") (pintype "passive"))
      (node (ref "ESD16") (pin "2") (pinfunction "2_2") (pintype "passive"))
      (node (ref "ESD17") (pin "2") (pinfunction "2_2") (pintype "passive"))
      (node (ref "ESD18") (pin "2") (pinfunction "2_2") (pintype "passive"))
      (node (ref "ESD19") (pin "2") (pinfunction "2_2") (pintype "passive"))
      (node (ref "ESD2") (pin "2") (pinfunction "2_2") (pintype "passive"))
      (node (ref "ESD20") (pin "2") (pinfunction "2_2") (pintype "passive"))
      (node (ref "ESD21") (pin "2") (pinfunction "2_2") (pintype "passive"))
      (node (ref "ESD22") (pin "2") (pinfunction "2_2") (pintype "passive"))
      (node (ref "ESD23") (pin "2") (pinfunction "2_2") (pintype "passive"))
      (node (ref "ESD24") (pin "2") (pinfunction "2_2") (pintype "passive"))
      (node (ref "ESD25") (pin "2") (pinfunction "2_2") (pintype "passive"))
      (node (ref "ESD26") (pin "2") (pinfunction "2_2") (pintype "passive"))
      (node (ref "ESD27") (pin "2") (pinfunction "2_2") (pintype "passive"))
      (node (ref "ESD28") (pin "2") (pinfunction "2_2") (pintype "passive"))
      (node (ref "ESD29") (pin "2") (pinfunction "2_2") (pintype "passive"))
      (node (ref "ESD3") (pin "2") (pinfunction "2_2") (pintype "passive"))
      (node (ref "ESD30") (pin "2") (pinfunction "2_2") (pintype "passive"))
      (node (ref "ESD31") (pin "2") (pinfunction "2_2") (pintype "passive"))
      (node (ref "ESD32") (pin "2") (pinfunction "2_2") (pintype "passive"))
      (node (ref "ESD33") (pin "2") (pinfunction "2_2") (pintype "passive"))
      (node (ref "ESD4") (pin "2") (pinfunction "2_2") (pintype "passive"))
      (node (ref "ESD5") (pin "2") (pinfunction "2_2") (pintype "passive"))
      (node (ref "ESD6") (pin "2") (pinfunction "2_2") (pintype "passive"))
      (node (ref "ESD7") (pin "2") (pinfunction "2_2") (pintype "passive"))
      (node (ref "ESD8") (pin "2") (pinfunction "2_2") (pintype "passive"))
      (node (ref "ESD9") (pin "2") (pinfunction "2_2") (pintype "passive"))
      (node (ref "IC25") (pin "2") (pinfunction "GND_2") (pintype "passive"))
      (node (ref "IC26") (pin "3") (pinfunction "GND_3") (pintype "passive"))
      (node (ref "IC26") (pin "8") (pinfunction "~{OE}_8") (pintype "input"))
      (node (ref "IC27") (pin "3") (pinfunction "GND_3") (pintype "passive"))
      (node (ref "IC27") (pin "8") (pinfunction "~{OE}_8") (pintype "input"))
      (node (ref "IC28") (pin "2") (pinfunction "GND_2") (pintype "passive"))
      (node (ref "IC29") (pin "12") (pinfunction "GND_12") (pintype "passive"))
      (node (ref "IC29") (pin "18") (pinfunction "GND_18") (pintype "passive"))
      (node (ref "IC29") (pin "3") (pinfunction "GND_3") (pintype "passive"))
      (node (ref "IC29") (pin "7") (pinfunction "~{OE}_7") (pintype "input"))
      (node (ref "IC29") (pin "PAD") (pinfunction "GND_PAD") (pintype "passive"))
      (node (ref "IC30") (pin "12") (pinfunction "GND_12") (pintype "passive"))
      (node (ref "IC30") (pin "18") (pinfunction "GND_18") (pintype "passive"))
      (node (ref "IC30") (pin "3") (pinfunction "GND_3") (pintype "passive"))
      (node (ref "IC30") (pin "7") (pinfunction "~{OE}_7") (pintype "input"))
      (node (ref "IC30") (pin "PAD") (pinfunction "GND_PAD") (pintype "passive"))
      (node (ref "J29") (pin "13") (pinfunction "GND_13") (pintype "passive"))
      (node (ref "J29") (pin "16") (pinfunction "GND_DRAIN_16") (pintype "passive"))
      (node (ref "J29") (pin "4") (pinfunction "GND_4") (pintype "passive"))
      (node (ref "J29") (pin "7") (pinfunction "GND_DRAIN_7") (pintype "passive"))
      (node (ref "J29") (pin "SHIELD") (pinfunction "4x_SHIELD_PINS_SHIELD") (pintype "passive"))
      (node (ref "J30") (pin "11") (pinfunction "TMDS_CLOCK_SHIELD_11") (pintype "passive"))
      (node (ref "J30") (pin "17") (pinfunction "GND_17") (pintype "power_in"))
      (node (ref "J30") (pin "2") (pinfunction "TMDS_DATA_2_SHIELD_2") (pintype "passive"))
      (node (ref "J30") (pin "5") (pinfunction "TMDS_DATA_1_SHIELD_5") (pintype "passive"))
      (node (ref "J30") (pin "8") (pinfunction "TMDS_DATA_0_SHIELD_8") (pintype "passive"))
      (node (ref "J30") (pin "S1") (pinfunction "SHIELD_S1") (pintype "passive"))
      (node (ref "J30") (pin "S2") (pinfunction "SHIELD_S2") (pintype "passive"))
      (node (ref "J30") (pin "S3") (pinfunction "SHIELD_S3") (pintype "passive"))
      (node (ref "J30") (pin "S4") (pinfunction "SHIELD_S4") (pintype "passive"))
      (node (ref "J31") (pin "11") (pinfunction "TMDS_CLOCK_SHIELD_11") (pintype "passive"))
      (node (ref "J31") (pin "17") (pinfunction "GND_17") (pintype "power_in"))
      (node (ref "J31") (pin "2") (pinfunction "TMDS_DATA_2_SHIELD_2") (pintype "passive"))
      (node (ref "J31") (pin "5") (pinfunction "TMDS_DATA_1_SHIELD_5") (pintype "passive"))
      (node (ref "J31") (pin "8") (pinfunction "TMDS_DATA_0_SHIELD_8") (pintype "passive"))
      (node (ref "J31") (pin "S1") (pinfunction "SHIELD_S1") (pintype "passive"))
      (node (ref "J31") (pin "S2") (pinfunction "SHIELD_S2") (pintype "passive"))
      (node (ref "J31") (pin "S3") (pinfunction "SHIELD_S3") (pintype "passive"))
      (node (ref "J31") (pin "S4") (pinfunction "SHIELD_S4") (pintype "passive"))
      (node (ref "R132") (pin "2") (pinfunction "2_2") (pintype "passive"))
      (node (ref "R138") (pin "1") (pinfunction "1_1") (pintype "passive"))
      (node (ref "R144") (pin "1") (pinfunction "1_1") (pintype "passive"))
      (node (ref "VD14") (pin "K") (pinfunction "K_K") (pintype "passive"))
      (node (ref "VD15") (pin "K") (pinfunction "K_K") (pintype "passive"))
      (node (ref "VD16") (pin "K") (pinfunction "K_K") (pintype "passive"))
      (node (ref "VD17") (pin "K") (pinfunction "K_K") (pintype "passive"))
    )
    (net (code "58") (name "Net-(IC25-CSLEW)") (class "Default")
      (node (ref "C83") (pin "1") (pinfunction "1_1") (pintype "passive"))
      (node (ref "IC25") (pin "5") (pinfunction "CSLEW_5") (pintype "output"))
      (node (ref "R136") (pin "1") (pinfunction "1_1") (pintype "passive"))
      (node (ref "R138") (pin "2") (pinfunction "2_2") (pintype "passive"))
    )
    (net (code "59") (name "Net-(IC25-EN)") (class "Default")
      (node (ref "IC25") (pin "3") (pinfunction "EN_3") (pintype "input"))
      (node (ref "R134") (pin "1") (pinfunction "1_1") (pintype "passive"))
      (node (ref "R135") (pin "1") (pinfunction "1_1") (pintype "passive"))
      (node (ref "R137") (pin "1") (pinfunction "1_1") (pintype "passive"))
    )
    (net (code "60") (name "Net-(IC25-FAULT{slash})") (class "Default")
      (node (ref "IC25") (pin "4") (pinfunction "FAULT/_4") (pintype "output"))
      (node (ref "R139") (pin "1") (pinfunction "1_1") (pintype "passive"))
    )
    (net (code "61") (name "Net-(IC28-CSLEW)") (class "Default")
      (node (ref "C88") (pin "1") (pinfunction "1_1") (pintype "passive"))
      (node (ref "IC28") (pin "5") (pinfunction "CSLEW_5") (pintype "output"))
      (node (ref "R142") (pin "1") (pinfunction "1_1") (pintype "passive"))
      (node (ref "R144") (pin "2") (pinfunction "2_2") (pintype "passive"))
    )
    (net (code "62") (name "Net-(IC28-EN)") (class "Default")
      (node (ref "IC28") (pin "3") (pinfunction "EN_3") (pintype "input"))
      (node (ref "R141") (pin "1") (pinfunction "1_1") (pintype "passive"))
    )
    (net (code "63") (name "Net-(IC28-FAULT{slash})") (class "Default")
      (node (ref "IC28") (pin "4") (pinfunction "FAULT/_4") (pintype "output"))
      (node (ref "R143") (pin "2") (pinfunction "2_2") (pintype "passive"))
    )
    (net (code "64") (name "Net-(IC29-SSTX2+)") (class "Default")
      (node (ref "C93") (pin "1") (pinfunction "1_1") (pintype "passive"))
      (node (ref "IC29") (pin "13") (pinfunction "SSTX2+_13") (pintype "bidirectional"))
    )
    (net (code "65") (name "Net-(IC29-SSTX2-)") (class "Default")
      (node (ref "C91") (pin "1") (pinfunction "1_1") (pintype "passive"))
      (node (ref "IC29") (pin "14") (pinfunction "SSTX2-_14") (pintype "bidirectional"))
    )
    (net (code "66") (name "Net-(IC30-SSTX2+)") (class "Default")
      (node (ref "C94") (pin "1") (pinfunction "1_1") (pintype "passive"))
      (node (ref "IC30") (pin "13") (pinfunction "SSTX2+_13") (pintype "bidirectional"))
    )
    (net (code "67") (name "Net-(IC30-SSTX2-)") (class "Default")
      (node (ref "C92") (pin "1") (pinfunction "1_1") (pintype "passive"))
      (node (ref "IC30") (pin "14") (pinfunction "SSTX2-_14") (pintype "bidirectional"))
    )
    (net (code "68") (name "VCC3P3") (class "Default")
      (node (ref "C89") (pin "1") (pinfunction "1_1") (pintype "passive"))
      (node (ref "C90") (pin "1") (pinfunction "1_1") (pintype "passive"))
      (node (ref "C95") (pin "1") (pinfunction "1_1") (pintype "passive"))
      (node (ref "C96") (pin "1") (pinfunction "1_1") (pintype "passive"))
      (node (ref "IC26") (pin "9") (pinfunction "VCC_9") (pintype "power_in"))
      (node (ref "IC27") (pin "9") (pinfunction "VCC_9") (pintype "power_in"))
      (node (ref "IC29") (pin "17") (pinfunction "VDD_17") (pintype "power_in"))
      (node (ref "IC30") (pin "17") (pinfunction "VDD_17") (pintype "power_in"))
      (node (ref "R131") (pin "2") (pinfunction "2_2") (pintype "passive"))
    )
    (net (code "69") (name "VCC5P0") (class "Default")
      (node (ref "C80") (pin "1") (pinfunction "1_1") (pintype "passive"))
      (node (ref "C83") (pin "2") (pinfunction "2_2") (pintype "passive"))
      (node (ref "C84") (pin "1") (pinfunction "1_1") (pintype "passive"))
      (node (ref "C88") (pin "2") (pinfunction "2_2") (pintype "passive"))
      (node (ref "IC25") (pin "1") (pinfunction "VIN_1") (pintype "input"))
      (node (ref "IC28") (pin "1") (pinfunction "VIN_1") (pintype "input"))
      (node (ref "R133") (pin "2") (pinfunction "2_2") (pintype "passive"))
      (node (ref "R134") (pin "2") (pinfunction "2_2") (pintype "passive"))
      (node (ref "R140") (pin "2") (pinfunction "2_2") (pintype "passive"))
      (node (ref "R141") (pin "2") (pinfunction "2_2") (pintype "passive"))
      (node (ref "R143") (pin "1") (pinfunction "1_1") (pintype "passive"))
    )
    (net (code "70") (name "VCC5P0_HDMI") (class "Default")
      (node (ref "C85") (pin "1") (pinfunction "1_1") (pintype "passive"))
      (node (ref "C86") (pin "1") (pinfunction "1_1") (pintype "passive"))
      (node (ref "C87") (pin "1") (pinfunction "1_1") (pintype "passive"))
      (node (ref "IC28") (pin "6") (pinfunction "VOUT_6") (pintype "output"))
      (node (ref "J30") (pin "18") (pinfunction "+5V_POWER_18") (pintype "power_in"))
      (node (ref "J31") (pin "18") (pinfunction "+5V_POWER_18") (pintype "power_in"))
      (node (ref "R140") (pin "1") (pinfunction "1_1") (pintype "passive"))
      (node (ref "R142") (pin "2") (pinfunction "2_2") (pintype "passive"))
    )
    (net (code "71") (name "VCC5P0_USBS") (class "Default")
      (node (ref "C79") (pin "2") (pinfunction "2_2") (pintype "passive"))
      (node (ref "C81") (pin "1") (pinfunction "1_1") (pintype "passive"))
      (node (ref "C82") (pin "2") (pinfunction "2_2") (pintype "passive"))
      (node (ref "IC25") (pin "6") (pinfunction "VOUT_6") (pintype "output"))
      (node (ref "J29") (pin "1") (pinfunction "VBUS_1") (pintype "power_in"))
      (node (ref "J29") (pin "10") (pinfunction "VBUS_10") (pintype "power_in"))
      (node (ref "R133") (pin "1") (pinfunction "1_1") (pintype "passive"))
      (node (ref "R136") (pin "2") (pinfunction "2_2") (pintype "passive"))
    )
    (net (code "72") (name "unconnected-(IC29-SSRX1+-Pad10)") (class "Default")
      (node (ref "IC29") (pin "10") (pinfunction "SSRX1+_10") (pintype "bidirectional+no_connect"))
    )
    (net (code "73") (name "unconnected-(IC29-SSRX1--Pad11)") (class "Default")
      (node (ref "IC29") (pin "11") (pinfunction "SSRX1-_11") (pintype "bidirectional+no_connect"))
    )
    (net (code "74") (name "unconnected-(IC29-SSTX1+-Pad15)") (class "Default")
      (node (ref "IC29") (pin "15") (pinfunction "SSTX1+_15") (pintype "bidirectional+no_connect"))
    )
    (net (code "75") (name "unconnected-(IC29-SSTX1--Pad16)") (class "Default")
      (node (ref "IC29") (pin "16") (pinfunction "SSTX1-_16") (pintype "bidirectional+no_connect"))
    )
    (net (code "76") (name "unconnected-(IC30-SSRX1+-Pad10)") (class "Default")
      (node (ref "IC30") (pin "10") (pinfunction "SSRX1+_10") (pintype "bidirectional+no_connect"))
    )
    (net (code "77") (name "unconnected-(IC30-SSRX1--Pad11)") (class "Default")
      (node (ref "IC30") (pin "11") (pinfunction "SSRX1-_11") (pintype "bidirectional+no_connect"))
    )
    (net (code "78") (name "unconnected-(IC30-SSTX1+-Pad15)") (class "Default")
      (node (ref "IC30") (pin "15") (pinfunction "SSTX1+_15") (pintype "bidirectional+no_connect"))
    )
    (net (code "79") (name "unconnected-(IC30-SSTX1--Pad16)") (class "Default")
      (node (ref "IC30") (pin "16") (pinfunction "SSTX1-_16") (pintype "bidirectional+no_connect"))
    )
  )
)
